# schema_actuator.net
KiCad netlist of a schematic drawn in EAGLE
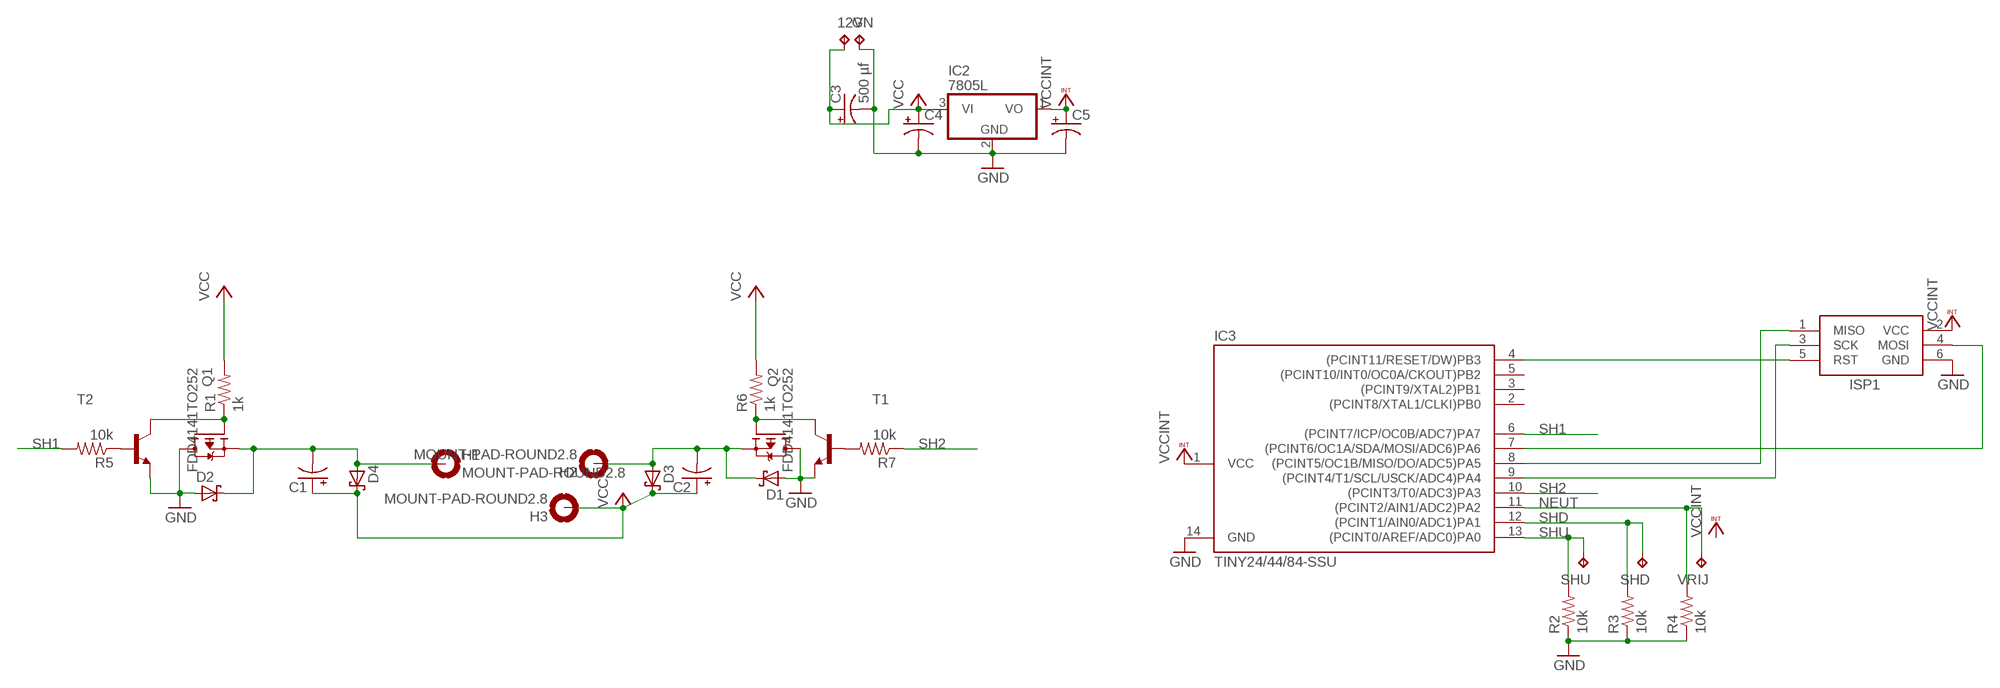
[diagram p0: schematic, sheet 1]

(export (version "E")
  (design (tool "Eeschema 10.0.6"))
  (components
    (comp (ref "12V")
      (value "TPPAD1-20Y")
      (footprint "eagle-import:P1-20Y")
      (libsource (lib "eagle-import") (part "TPPAD1-20Y"))
    )
    (comp (ref "C1")
      (value "CPOL-USD")
      (footprint "eagle-import:PANASONIC_D")
      (libsource (lib "eagle-import") (part "CPOL-USD"))
    )
    (comp (ref "C2")
      (value "CPOL-USD")
      (footprint "eagle-import:PANASONIC_D")
      (libsource (lib "eagle-import") (part "CPOL-USD"))
    )
    (comp (ref "C3")
      (value "500 µf")
      (footprint "eagle-import:PANASONIC_G")
      (libsource (lib "eagle-import") (part "CPOL-USG"))
    )
    (comp (ref "C4")
      (value "CPOL-USD")
      (footprint "eagle-import:PANASONIC_D")
      (libsource (lib "eagle-import") (part "CPOL-USD"))
    )
    (comp (ref "C5")
      (value "CPOL-USD")
      (footprint "eagle-import:PANASONIC_D")
      (libsource (lib "eagle-import") (part "CPOL-USD"))
    )
    (comp (ref "D1")
      (value "SCHOTTKY-DIODEDO41")
      (footprint "eagle-import:DO41-10")
      (libsource (lib "eagle-import") (part "SCHOTTKY-DIODEDO41"))
    )
    (comp (ref "D2")
      (value "SCHOTTKY-DIODEDO41")
      (footprint "eagle-import:DO41-10")
      (libsource (lib "eagle-import") (part "SCHOTTKY-DIODEDO41"))
    )
    (comp (ref "D3")
      (value "SCHOTTKY-DIODEDO41")
      (footprint "eagle-import:DO41-10")
      (libsource (lib "eagle-import") (part "SCHOTTKY-DIODEDO41"))
    )
    (comp (ref "D4")
      (value "SCHOTTKY-DIODEDO41")
      (footprint "eagle-import:DO41-10")
      (libsource (lib "eagle-import") (part "SCHOTTKY-DIODEDO41"))
    )
    (comp (ref "GN")
      (value "TPPAD1-20Y")
      (footprint "eagle-import:P1-20Y")
      (libsource (lib "eagle-import") (part "TPPAD1-20Y"))
    )
    (comp (ref "H1")
      (value "MOUNT-PAD-ROUND2.8")
      (footprint "eagle-import:2,8-PAD")
      (libsource (lib "eagle-import") (part "MOUNT-PAD-ROUND2.8"))
    )
    (comp (ref "H2")
      (value "MOUNT-PAD-ROUND2.8")
      (footprint "eagle-import:2,8-PAD")
      (libsource (lib "eagle-import") (part "MOUNT-PAD-ROUND2.8"))
    )
    (comp (ref "H3")
      (value "MOUNT-PAD-ROUND2.8")
      (footprint "eagle-import:2,8-PAD")
      (libsource (lib "eagle-import") (part "MOUNT-PAD-ROUND2.8"))
    )
    (comp (ref "IC2")
      (value "7805L")
      (footprint "eagle-import:TO92")
      (libsource (lib "eagle-import") (part "78L05"))
    )
    (comp (ref "IC3")
      (value "TINY24/44/84-SSU")
      (footprint "eagle-import:SOIC14")
      (libsource (lib "eagle-import") (part "TINY24/44/84-SSU"))
    )
    (comp (ref "ISP1")
      (value "AVRISP-6")
      (footprint "eagle-import:AVRISP")
      (libsource (lib "eagle-import") (part "AVRISP-6"))
    )
    (comp (ref "Q1")
      (value "FDD4141TO252")
      (footprint "eagle-import:TO252")
      (libsource (lib "eagle-import") (part "FDD4141TO252"))
    )
    (comp (ref "Q2")
      (value "FDD4141TO252")
      (footprint "eagle-import:TO252")
      (libsource (lib "eagle-import") (part "FDD4141TO252"))
    )
    (comp (ref "R1")
      (value "1k")
      (footprint "eagle-import:R1206")
      (libsource (lib "eagle-import") (part "R-US_R1206"))
    )
    (comp (ref "R2")
      (value "10k")
      (footprint "eagle-import:R1206")
      (libsource (lib "eagle-import") (part "R-US_R1206"))
    )
    (comp (ref "R3")
      (value "10k")
      (footprint "eagle-import:R1206")
      (libsource (lib "eagle-import") (part "R-US_R1206"))
    )
    (comp (ref "R4")
      (value "10k")
      (footprint "eagle-import:R1206")
      (libsource (lib "eagle-import") (part "R-US_R1206"))
    )
    (comp (ref "R5")
      (value "10k")
      (footprint "eagle-import:R1206")
      (libsource (lib "eagle-import") (part "R-US_R1206"))
    )
    (comp (ref "R6")
      (value "1k")
      (footprint "eagle-import:R1206")
      (libsource (lib "eagle-import") (part "R-US_R1206"))
    )
    (comp (ref "R7")
      (value "10k")
      (footprint "eagle-import:R1206")
      (libsource (lib "eagle-import") (part "R-US_R1206"))
    )
    (comp (ref "SHD")
      (value "TPPAD1-20Y")
      (footprint "eagle-import:P1-20Y")
      (libsource (lib "eagle-import") (part "TPPAD1-20Y"))
    )
    (comp (ref "SHU")
      (value "TPPAD1-20Y")
      (footprint "eagle-import:P1-20Y")
      (libsource (lib "eagle-import") (part "TPPAD1-20Y"))
    )
    (comp (ref "T1")
      (value "BC817-40-NPN-SOT23-BEC")
      (footprint "eagle-import:SOT23-BEC")
      (libsource (lib "eagle-import") (part "-NPN-SOT23-BECBC817-40"))
    )
    (comp (ref "T2")
      (value "BC817-40-NPN-SOT23-BEC")
      (footprint "eagle-import:SOT23-BEC")
      (libsource (lib "eagle-import") (part "-NPN-SOT23-BECBC817-40"))
    )
    (comp (ref "VRIJ")
      (value "TPPAD1-20Y")
      (footprint "eagle-import:P1-20Y")
      (libsource (lib "eagle-import") (part "TPPAD1-20Y"))
    )
  )
  (nets
    (net (code "1") (name "/NEUT") (class "Default")
      (node (ref "IC3") (pin "11") (pinfunction "(PCINT2/AIN1/ADC2)PA2_11") (pintype "bidirectional"))
      (node (ref "R4") (pin "2") (pinfunction "2_2") (pintype "passive"))
      (node (ref "VRIJ") (pin "TP") (pinfunction "TP_TP") (pintype "input"))
    )
    (net (code "2") (name "/SH1") (class "Default")
      (node (ref "IC3") (pin "6") (pinfunction "(PCINT7/ICP/OC0B/ADC7)PA7_6") (pintype "bidirectional"))
      (node (ref "R5") (pin "2") (pinfunction "2_2") (pintype "passive"))
    )
    (net (code "3") (name "/SH2") (class "Default")
      (node (ref "IC3") (pin "10") (pinfunction "(PCINT3/T0/ADC3)PA3_10") (pintype "bidirectional"))
      (node (ref "R7") (pin "1") (pinfunction "1_1") (pintype "passive"))
    )
    (net (code "4") (name "/SHD") (class "Default")
      (node (ref "IC3") (pin "12") (pinfunction "(PCINT1/AIN0/ADC1)PA1_12") (pintype "bidirectional"))
      (node (ref "R3") (pin "2") (pinfunction "2_2") (pintype "passive"))
      (node (ref "SHD") (pin "TP") (pinfunction "TP_TP") (pintype "input"))
    )
    (net (code "5") (name "/SHU") (class "Default")
      (node (ref "IC3") (pin "13") (pinfunction "(PCINT0/AREF/ADC0)PA0_13") (pintype "bidirectional"))
      (node (ref "R2") (pin "2") (pinfunction "2_2") (pintype "passive"))
      (node (ref "SHU") (pin "TP") (pinfunction "TP_TP") (pintype "input"))
    )
    (net (code "6") (name "GND") (class "Default")
      (node (ref "C3") (pin "-") (pinfunction "-_-") (pintype "passive"))
      (node (ref "C4") (pin "-") (pinfunction "-_-") (pintype "passive"))
      (node (ref "C5") (pin "-") (pinfunction "-_-") (pintype "passive"))
      (node (ref "D1") (pin "A") (pinfunction "A_A") (pintype "passive"))
      (node (ref "D2") (pin "A") (pinfunction "A_A") (pintype "passive"))
      (node (ref "GN") (pin "TP") (pinfunction "TP_TP") (pintype "input"))
      (node (ref "IC2") (pin "2") (pinfunction "GND_2") (pintype "passive"))
      (node (ref "IC3") (pin "14") (pinfunction "GND_14") (pintype "power_in"))
      (node (ref "ISP1") (pin "6") (pinfunction "GND_6") (pintype "power_in"))
      (node (ref "Q1") (pin "3") (pinfunction "D_3") (pintype "passive"))
      (node (ref "Q2") (pin "3") (pinfunction "D_3") (pintype "passive"))
      (node (ref "R2") (pin "1") (pinfunction "1_1") (pintype "passive"))
      (node (ref "R3") (pin "1") (pinfunction "1_1") (pintype "passive"))
      (node (ref "R4") (pin "1") (pinfunction "1_1") (pintype "passive"))
      (node (ref "T1") (pin "E") (pinfunction "E_E") (pintype "passive"))
      (node (ref "T2") (pin "E") (pinfunction "E_E") (pintype "passive"))
    )
    (net (code "7") (name "Net-(H1-MOUNT)") (class "Default")
      (node (ref "C1") (pin "-") (pinfunction "-_-") (pintype "passive"))
      (node (ref "D2") (pin "C") (pinfunction "C_C") (pintype "passive"))
      (node (ref "D4") (pin "A") (pinfunction "A_A") (pintype "passive"))
      (node (ref "H1") (pin "B2,8") (pinfunction "MOUNT_B2,8") (pintype "passive"))
      (node (ref "Q1") (pin "2") (pinfunction "S_2") (pintype "passive"))
    )
    (net (code "8") (name "Net-(H2-MOUNT)") (class "Default")
      (node (ref "C2") (pin "-") (pinfunction "-_-") (pintype "passive"))
      (node (ref "D1") (pin "C") (pinfunction "C_C") (pintype "passive"))
      (node (ref "D3") (pin "A") (pinfunction "A_A") (pintype "passive"))
      (node (ref "H2") (pin "B2,8") (pinfunction "MOUNT_B2,8") (pintype "passive"))
      (node (ref "Q2") (pin "2") (pinfunction "S_2") (pintype "passive"))
    )
    (net (code "9") (name "Net-(IC3-(PCINT4{slash}T1{slash}SCL{slash}USCK{slash}ADC4)PA4)") (class "Default")
      (node (ref "IC3") (pin "9") (pinfunction "(PCINT4/T1/SCL/USCK/ADC4)PA4_9") (pintype "bidirectional"))
      (node (ref "ISP1") (pin "3") (pinfunction "SCK_3") (pintype "output"))
    )
    (net (code "10") (name "Net-(IC3-(PCINT5{slash}OC1B{slash}MISO{slash}DO{slash}ADC5)PA5)") (class "Default")
      (node (ref "IC3") (pin "8") (pinfunction "(PCINT5/OC1B/MISO/DO/ADC5)PA5_8") (pintype "bidirectional"))
      (node (ref "ISP1") (pin "1") (pinfunction "MISO_1") (pintype "input"))
    )
    (net (code "11") (name "Net-(IC3-(PCINT6{slash}OC1A{slash}SDA{slash}MOSI{slash}ADC6)PA6)") (class "Default")
      (node (ref "IC3") (pin "7") (pinfunction "(PCINT6/OC1A/SDA/MOSI/ADC6)PA6_7") (pintype "bidirectional"))
      (node (ref "ISP1") (pin "4") (pinfunction "MOSI_4") (pintype "output"))
    )
    (net (code "12") (name "Net-(IC3-(PCINT11{slash}RESET{slash}DW)PB3)") (class "Default")
      (node (ref "IC3") (pin "4") (pinfunction "(PCINT11/RESET/DW)PB3_4") (pintype "bidirectional"))
      (node (ref "ISP1") (pin "5") (pinfunction "RST_5") (pintype "output"))
    )
    (net (code "13") (name "Net-(Q1-G)") (class "Default")
      (node (ref "Q1") (pin "1") (pinfunction "G_1") (pintype "passive"))
      (node (ref "R1") (pin "1") (pinfunction "1_1") (pintype "passive"))
      (node (ref "T2") (pin "C") (pinfunction "C_C") (pintype "passive"))
    )
    (net (code "14") (name "Net-(Q2-G)") (class "Default")
      (node (ref "Q2") (pin "1") (pinfunction "G_1") (pintype "passive"))
      (node (ref "R6") (pin "1") (pinfunction "1_1") (pintype "passive"))
      (node (ref "T1") (pin "C") (pinfunction "C_C") (pintype "passive"))
    )
    (net (code "15") (name "Net-(R5-Pad1)") (class "Default")
      (node (ref "R5") (pin "1") (pinfunction "1_1") (pintype "passive"))
      (node (ref "T2") (pin "B") (pinfunction "B_B") (pintype "passive"))
    )
    (net (code "16") (name "Net-(R7-Pad2)") (class "Default")
      (node (ref "R7") (pin "2") (pinfunction "2_2") (pintype "passive"))
      (node (ref "T1") (pin "B") (pinfunction "B_B") (pintype "passive"))
    )
    (net (code "17") (name "VCC") (class "Default")
      (node (ref "12V") (pin "TP") (pinfunction "TP_TP") (pintype "input"))
      (node (ref "C1") (pin "+") (pinfunction "+_+") (pintype "passive"))
      (node (ref "C2") (pin "+") (pinfunction "+_+") (pintype "passive"))
      (node (ref "C3") (pin "+") (pinfunction "+_+") (pintype "passive"))
      (node (ref "C4") (pin "+") (pinfunction "+_+") (pintype "passive"))
      (node (ref "D3") (pin "C") (pinfunction "C_C") (pintype "passive"))
      (node (ref "D4") (pin "C") (pinfunction "C_C") (pintype "passive"))
      (node (ref "H3") (pin "B2,8") (pinfunction "MOUNT_B2,8") (pintype "passive"))
      (node (ref "IC2") (pin "3") (pinfunction "VI_3") (pintype "input"))
      (node (ref "R1") (pin "2") (pinfunction "2_2") (pintype "passive"))
      (node (ref "R6") (pin "2") (pinfunction "2_2") (pintype "passive"))
    )
    (net (code "18") (name "VCCINT") (class "Default")
      (node (ref "C5") (pin "+") (pinfunction "+_+") (pintype "passive"))
      (node (ref "IC2") (pin "1") (pinfunction "VO_1") (pintype "passive"))
      (node (ref "IC3") (pin "1") (pinfunction "VCC_1") (pintype "power_in"))
      (node (ref "ISP1") (pin "2") (pinfunction "VCC_2") (pintype "power_in"))
    )
    (net (code "19") (name "unconnected-(IC3-(PCINT8{slash}XTAL1{slash}CLKI)PB0-Pad2)") (class "Default")
      (node (ref "IC3") (pin "2") (pinfunction "(PCINT8/XTAL1/CLKI)PB0_2") (pintype "bidirectional"))
    )
    (net (code "20") (name "unconnected-(IC3-(PCINT9{slash}XTAL2)PB1-Pad3)") (class "Default")
      (node (ref "IC3") (pin "3") (pinfunction "(PCINT9/XTAL2)PB1_3") (pintype "bidirectional"))
    )
    (net (code "21") (name "unconnected-(IC3-(PCINT10{slash}INT0{slash}OC0A{slash}CKOUT)PB2-Pad5)") (class "Default")
      (node (ref "IC3") (pin "5") (pinfunction "(PCINT10/INT0/OC0A/CKOUT)PB2_5") (pintype "bidirectional"))
    )
  )
)
